# flash_mem.net
KiCad netlist of a schematic drawn in EAGLE
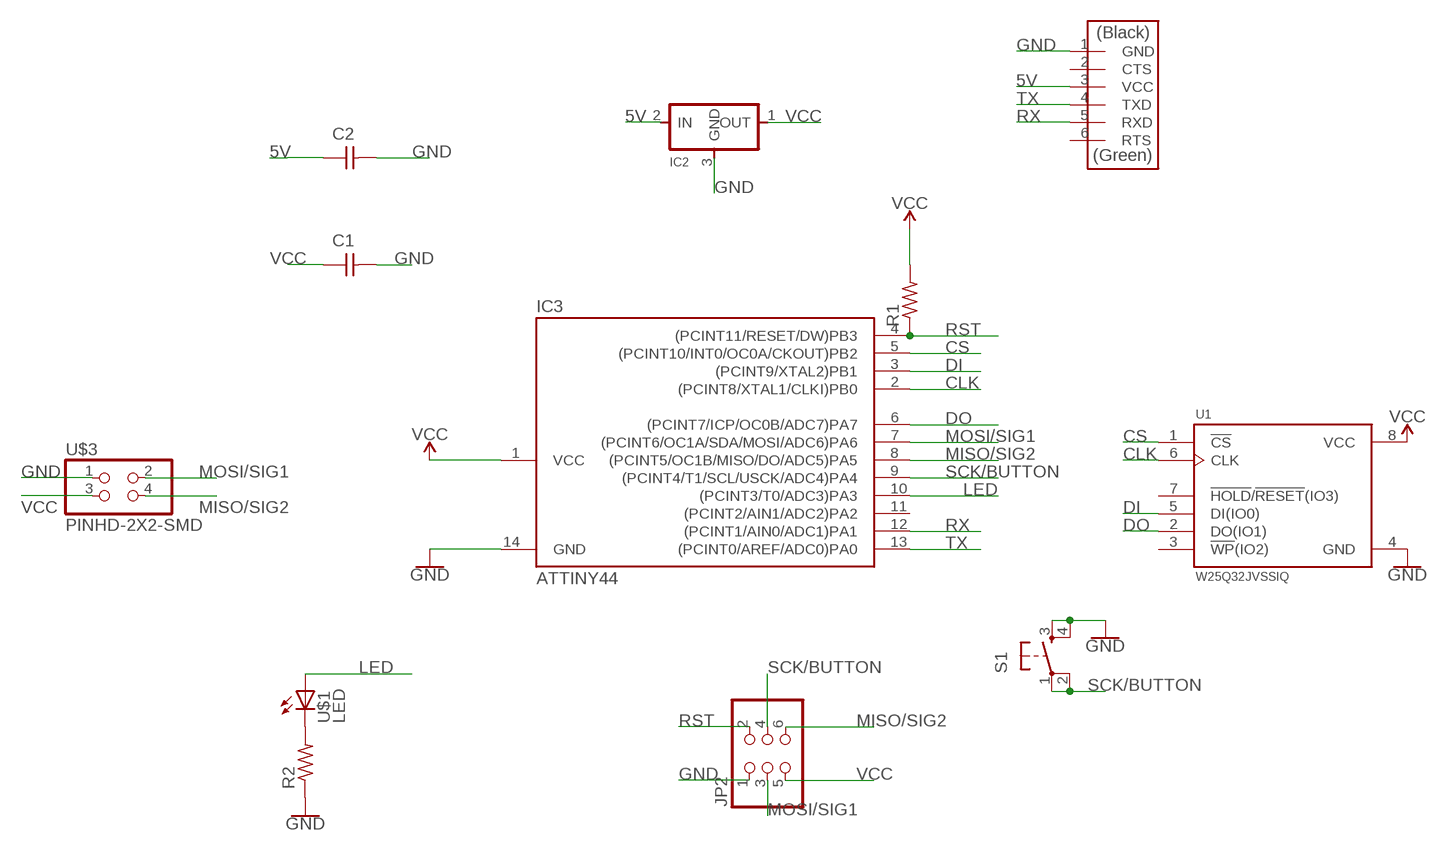
[diagram p0: schematic, sheet 1]

(export (version "E")
  (design (tool "Eeschema 10.0.6"))
  (components
    (comp (ref "C1")
      (value "CAP-UNPOLARIZED")
      (footprint "eagle-import:C1206")
      (libsource (lib "eagle-import") (part "CAP-UNPOLARIZED"))
    )
    (comp (ref "C2")
      (value "CAP-UNPOLARIZED")
      (footprint "eagle-import:C1206")
      (libsource (lib "eagle-import") (part "CAP-UNPOLARIZED"))
    )
    (comp (ref "IC2")
      (value "REGULATORSOT23")
      (footprint "eagle-import:SOT23")
      (libsource (lib "eagle-import") (part "REGULATORSOT23"))
    )
    (comp (ref "IC3")
      (value "ATTINY44")
      (footprint "eagle-import:SOIC14_MOD")
      (libsource (lib "eagle-import") (part "ATTINY44"))
    )
    (comp (ref "JP2")
      (value "PINHD-2X3-SMD")
      (footprint "eagle-import:2X03SMD")
      (libsource (lib "eagle-import") (part "PINHD-2X3-SMD"))
    )
    (comp (ref "R1")
      (value "RES-US1206")
      (footprint "eagle-import:R1206")
      (libsource (lib "eagle-import") (part "RES-US1206"))
    )
    (comp (ref "R2")
      (value "RES-US1206")
      (footprint "eagle-import:R1206")
      (libsource (lib "eagle-import") (part "RES-US1206"))
    )
    (comp (ref "S1")
      (value "6MM_SWITCH6MM_SWITCH")
      (footprint "eagle-import:6MM_SWITCH")
      (libsource (lib "eagle-import") (part "6MM_SWITCH6MM_SWITCH"))
    )
    (comp (ref "U$1")
      (value "LED")
      (footprint "eagle-import:LED1206")
      (libsource (lib "eagle-import") (part "LED"))
    )
    (comp (ref "U$2")
      (value "FTDI-SMD-HEADER")
      (footprint "eagle-import:1X06SMD")
      (libsource (lib "eagle-import") (part "FTDI-SMD-HEADER"))
    )
    (comp (ref "U$3")
      (value "PINHD-2X2-SMD")
      (footprint "eagle-import:2X02SMD")
      (libsource (lib "eagle-import") (part "PINHD-2X2-SMD"))
    )
    (comp (ref "U1")
      (value "W25Q32JVSSIQ")
      (footprint "eagle-import:SOIC127P790X216-8N")
      (fields (field (name "MF") "Winbond"))
      (libsource (lib "eagle-import") (part "W25Q32JVSSIQ"))
    )
  )
  (nets
    (net (code "1") (name "/5V") (class "Default")
      (node (ref "C2") (pin "1") (pinfunction "1_1") (pintype "passive"))
      (node (ref "IC2") (pin "2") (pinfunction "IN_2") (pintype "bidirectional"))
      (node (ref "U$2") (pin "3") (pinfunction "VCC_3") (pintype "bidirectional"))
    )
    (net (code "2") (name "/CLK") (class "Default")
      (node (ref "IC3") (pin "2") (pinfunction "(PCINT8/XTAL1/CLKI)PB0_2") (pintype "bidirectional"))
      (node (ref "U1") (pin "6") (pinfunction "CLK_6") (pintype "input"))
    )
    (net (code "3") (name "/CS") (class "Default")
      (node (ref "IC3") (pin "5") (pinfunction "(PCINT10/INT0/OC0A/CKOUT)PB2_5") (pintype "bidirectional"))
      (node (ref "U1") (pin "1") (pinfunction "~{CS}_1") (pintype "input"))
    )
    (net (code "4") (name "/DI") (class "Default")
      (node (ref "IC3") (pin "3") (pinfunction "(PCINT9/XTAL2)PB1_3") (pintype "bidirectional"))
      (node (ref "U1") (pin "5") (pinfunction "DI(IO0)_5") (pintype "bidirectional"))
    )
    (net (code "5") (name "/DO") (class "Default")
      (node (ref "IC3") (pin "6") (pinfunction "(PCINT7/ICP/OC0B/ADC7)PA7_6") (pintype "bidirectional"))
      (node (ref "U1") (pin "2") (pinfunction "DO(IO1)_2") (pintype "bidirectional"))
    )
    (net (code "6") (name "/LED") (class "Default")
      (node (ref "IC3") (pin "10") (pinfunction "(PCINT3/T0/ADC3)PA3_10") (pintype "bidirectional"))
      (node (ref "U$1") (pin "1") (pinfunction "A_1") (pintype "passive"))
    )
    (net (code "7") (name "/MISO{slash}SIG2") (class "Default")
      (node (ref "IC3") (pin "8") (pinfunction "(PCINT5/OC1B/MISO/DO/ADC5)PA5_8") (pintype "bidirectional"))
      (node (ref "JP2") (pin "6") (pinfunction "6_6") (pintype "passive"))
      (node (ref "U$3") (pin "4") (pinfunction "4_4") (pintype "passive"))
    )
    (net (code "8") (name "/MOSI{slash}SIG1") (class "Default")
      (node (ref "IC3") (pin "7") (pinfunction "(PCINT6/OC1A/SDA/MOSI/ADC6)PA6_7") (pintype "bidirectional"))
      (node (ref "JP2") (pin "3") (pinfunction "3_3") (pintype "passive"))
      (node (ref "U$3") (pin "2") (pinfunction "2_2") (pintype "passive"))
    )
    (net (code "9") (name "/RST") (class "Default")
      (node (ref "IC3") (pin "4") (pinfunction "(PCINT11/RESET/DW)PB3_4") (pintype "bidirectional"))
      (node (ref "JP2") (pin "2") (pinfunction "2_2") (pintype "passive"))
      (node (ref "R1") (pin "1") (pinfunction "1_1") (pintype "passive"))
    )
    (net (code "10") (name "/RX") (class "Default")
      (node (ref "IC3") (pin "12") (pinfunction "(PCINT1/AIN0/ADC1)PA1_12") (pintype "bidirectional"))
      (node (ref "U$2") (pin "5") (pinfunction "RXD_5") (pintype "bidirectional"))
    )
    (net (code "11") (name "/SCK{slash}BUTTON") (class "Default")
      (node (ref "IC3") (pin "9") (pinfunction "(PCINT4/T1/SCL/USCK/ADC4)PA4_9") (pintype "bidirectional"))
      (node (ref "JP2") (pin "4") (pinfunction "4_4") (pintype "passive"))
      (node (ref "S1") (pin "1") (pinfunction "P_1") (pintype "passive"))
      (node (ref "S1") (pin "2") (pinfunction "P1_2") (pintype "passive"))
    )
    (net (code "12") (name "/TX") (class "Default")
      (node (ref "IC3") (pin "13") (pinfunction "(PCINT0/AREF/ADC0)PA0_13") (pintype "bidirectional"))
      (node (ref "U$2") (pin "4") (pinfunction "TXD_4") (pintype "bidirectional"))
    )
    (net (code "13") (name "GND") (class "Default")
      (node (ref "C1") (pin "2") (pinfunction "2_2") (pintype "passive"))
      (node (ref "C2") (pin "2") (pinfunction "2_2") (pintype "passive"))
      (node (ref "IC2") (pin "3") (pinfunction "GND_3") (pintype "bidirectional"))
      (node (ref "IC3") (pin "14") (pinfunction "GND_14") (pintype "power_in"))
      (node (ref "JP2") (pin "1") (pinfunction "1_1") (pintype "passive"))
      (node (ref "R2") (pin "1") (pinfunction "1_1") (pintype "passive"))
      (node (ref "S1") (pin "3") (pinfunction "S_3") (pintype "passive"))
      (node (ref "S1") (pin "4") (pinfunction "S1_4") (pintype "passive"))
      (node (ref "U$2") (pin "1") (pinfunction "GND_1") (pintype "bidirectional"))
      (node (ref "U$3") (pin "1") (pinfunction "1_1") (pintype "passive"))
      (node (ref "U1") (pin "4") (pinfunction "GND_4") (pintype "power_in"))
    )
    (net (code "14") (name "Net-(U$1-C)") (class "Default")
      (node (ref "R2") (pin "2") (pinfunction "2_2") (pintype "passive"))
      (node (ref "U$1") (pin "2") (pinfunction "C_2") (pintype "passive"))
    )
    (net (code "15") (name "VCC") (class "Default")
      (node (ref "C1") (pin "1") (pinfunction "1_1") (pintype "passive"))
      (node (ref "IC2") (pin "1") (pinfunction "OUT_1") (pintype "bidirectional"))
      (node (ref "IC3") (pin "1") (pinfunction "VCC_1") (pintype "power_in"))
      (node (ref "JP2") (pin "5") (pinfunction "5_5") (pintype "passive"))
      (node (ref "R1") (pin "2") (pinfunction "2_2") (pintype "passive"))
      (node (ref "U$3") (pin "3") (pinfunction "3_3") (pintype "passive"))
      (node (ref "U1") (pin "8") (pinfunction "VCC_8") (pintype "power_in"))
    )
    (net (code "16") (name "unconnected-(IC3-(PCINT2{slash}AIN1{slash}ADC2)PA2-Pad11)") (class "Default")
      (node (ref "IC3") (pin "11") (pinfunction "(PCINT2/AIN1/ADC2)PA2_11") (pintype "bidirectional"))
    )
    (net (code "17") (name "unconnected-(U$2-CTS-Pad2)") (class "Default")
      (node (ref "U$2") (pin "2") (pinfunction "CTS_2") (pintype "bidirectional"))
    )
    (net (code "18") (name "unconnected-(U$2-RTS-Pad6)") (class "Default")
      (node (ref "U$2") (pin "6") (pinfunction "RTS_6") (pintype "bidirectional"))
    )
    (net (code "19") (name "unconnected-(U1-~{HOLD}{slash}~{RESET}(IO3)-Pad7)") (class "Default")
      (node (ref "U1") (pin "7") (pinfunction "~{HOLD}/~{RESET}(IO3)_7") (pintype "bidirectional"))
    )
    (net (code "20") (name "unconnected-(U1-~{WP}(IO2)-Pad3)") (class "Default")
      (node (ref "U1") (pin "3") (pinfunction "~{WP}(IO2)_3") (pintype "bidirectional"))
    )
  )
)
